# iBeacon.net
KiCad netlist of a schematic drawn in EAGLE
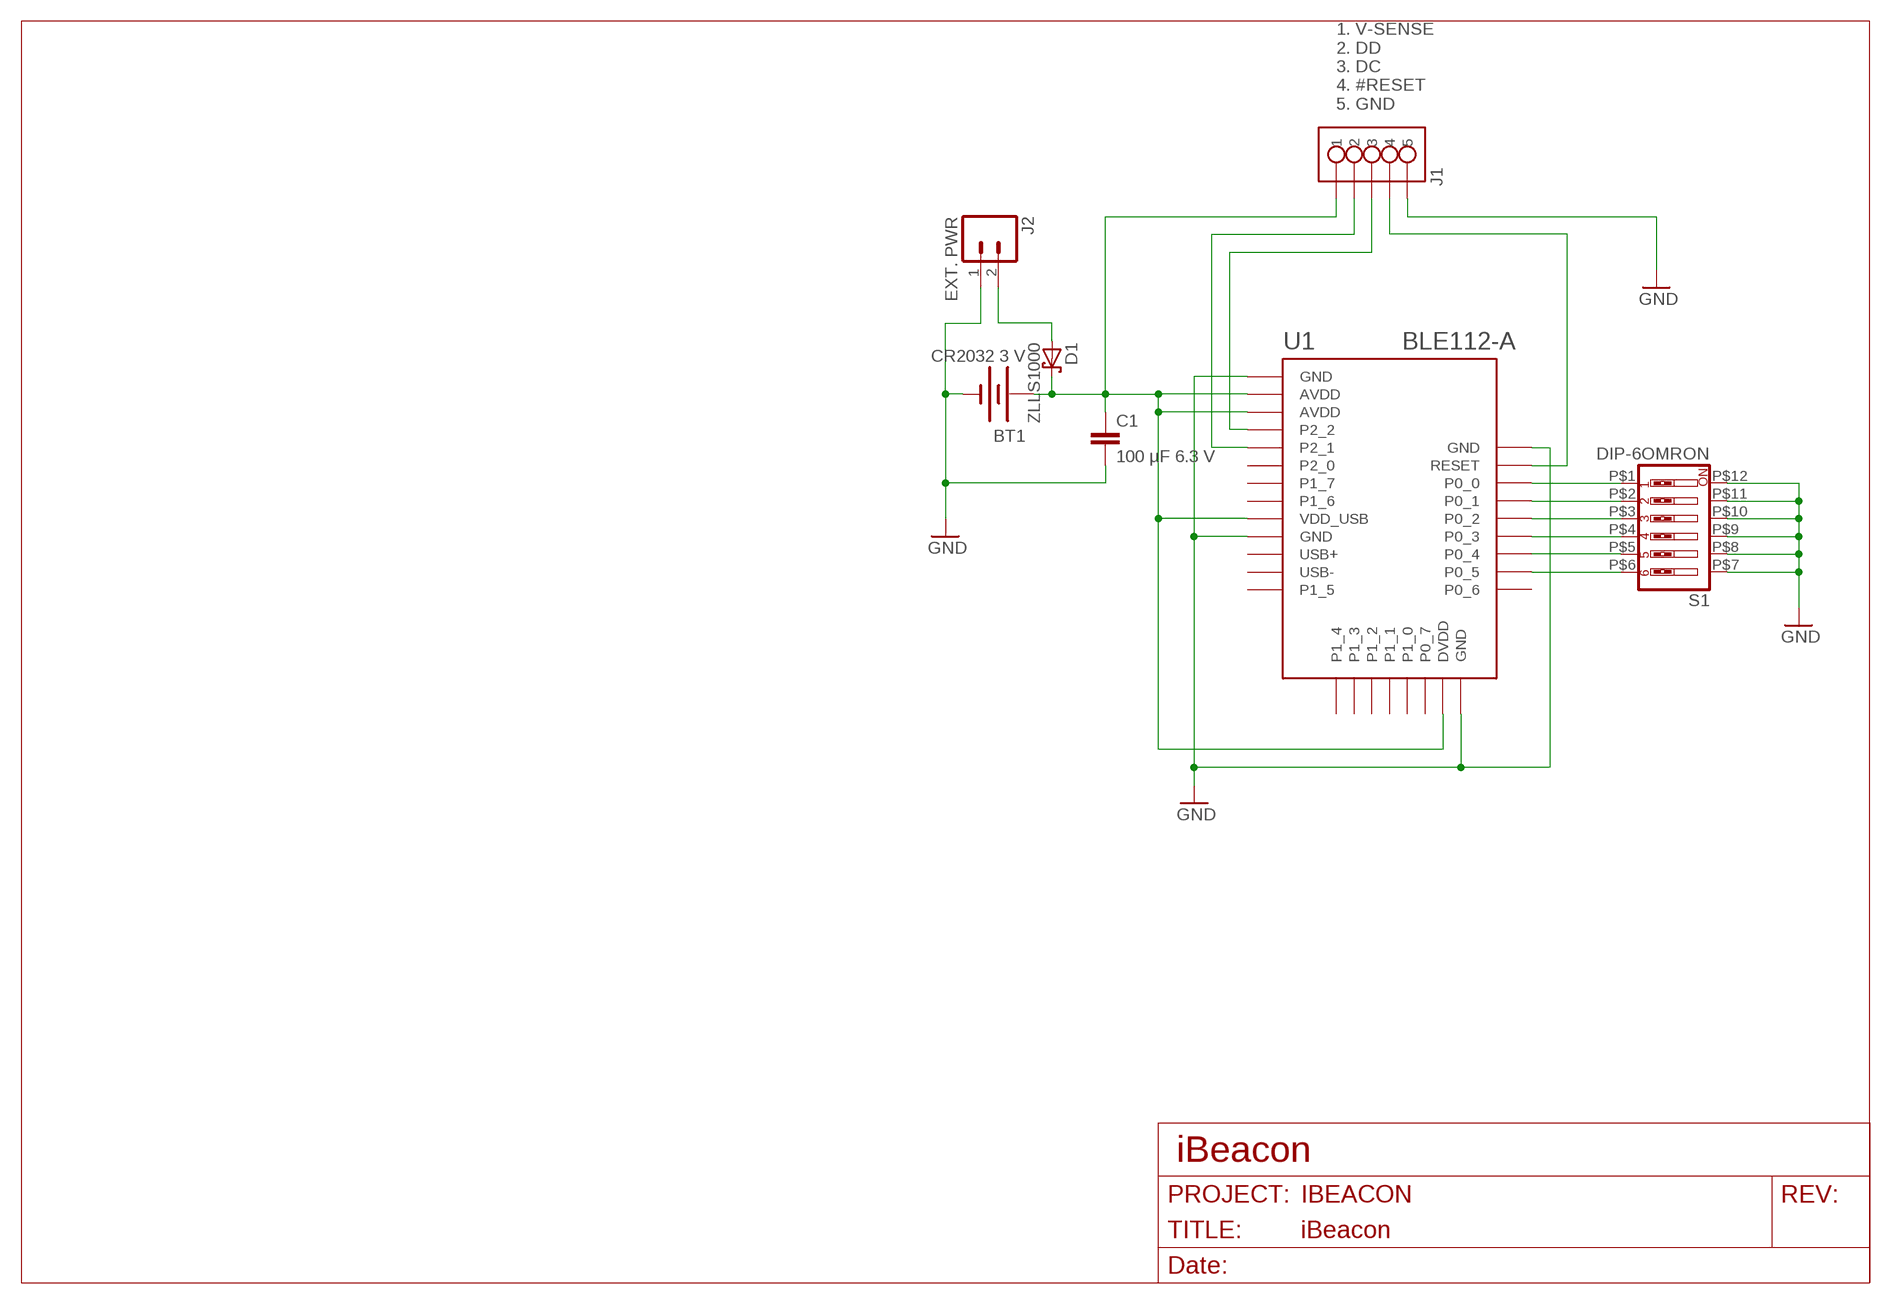
[diagram p0: schematic, sheet 1]

(export (version "E")
  (design (tool "Eeschema 10.0.6"))
  (components
    (comp (ref "BT1")
      (value "CR2032 3 V")
      (footprint "eagle-import:BATTCON_20MM")
      (libsource (lib "eagle-import") (part "BATTERY20SMD"))
    )
    (comp (ref "C1")
      (value "100 µF 6.3 V")
      (footprint "eagle-import:C1210K")
      (libsource (lib "eagle-import") (part "C-EUC1210K"))
    )
    (comp (ref "D1")
      (value "ZLLS1000")
      (footprint "eagle-import:SOT23")
      (libsource (lib "eagle-import") (part "BAS40"))
    )
    (comp (ref "IBEACON")
      (value "iBeacon")
      (footprint "eagle-import:DOCFIELD")
      (libsource (lib "eagle-import") (part "DOCFIELD_JWJ"))
    )
    (comp (ref "J1")
      (value "JST_SH_5")
      (footprint "eagle-import:JST_SH_5")
      (libsource (lib "eagle-import") (part "JST_SH_5"))
    )
    (comp (ref "J2")
      (value "EXT. PWR")
      (footprint "eagle-import:1X02")
      (libsource (lib "eagle-import") (part "M02PTH"))
    )
    (comp (ref "S1")
      (value "DIP-6OMRON")
      (footprint "eagle-import:OMRON_HALFPITCH_DIP_6")
      (libsource (lib "eagle-import") (part "DIP-6OMRON"))
    )
    (comp (ref "U1")
      (value "BLE112-A")
      (footprint "eagle-import:SF-BLUEGIGA_BLE112-A")
      (libsource (lib "eagle-import") (part "SF-BLUEGIGA_BLE112-A-VISUAL"))
    )
  )
  (nets
    (net (code "1") (name "GND") (class "Default")
      (node (ref "BT1") (pin "2") (pinfunction "-_2") (pintype "power_in"))
      (node (ref "C1") (pin "2") (pinfunction "2_2") (pintype "passive"))
      (node (ref "J1") (pin "P$5") (pinfunction "5_P$5") (pintype "bidirectional"))
      (node (ref "J2") (pin "1") (pinfunction "1_1") (pintype "passive"))
      (node (ref "S1") (pin "P$10") (pinfunction "10_P$10") (pintype "passive"))
      (node (ref "S1") (pin "P$11") (pinfunction "11_P$11") (pintype "passive"))
      (node (ref "S1") (pin "P$12") (pinfunction "12_P$12") (pintype "passive"))
      (node (ref "S1") (pin "P$7") (pinfunction "7_P$7") (pintype "passive"))
      (node (ref "S1") (pin "P$8") (pinfunction "8_P$8") (pintype "passive"))
      (node (ref "S1") (pin "P$9") (pinfunction "9_P$9") (pintype "passive"))
      (node (ref "U1") (pin "GND1") (pinfunction "GND_GND1") (pintype "power_in"))
      (node (ref "U1") (pin "GND2") (pinfunction "GND_GND2") (pintype "power_in"))
      (node (ref "U1") (pin "GND3") (pinfunction "GND_GND3") (pintype "power_in"))
      (node (ref "U1") (pin "GND4") (pinfunction "GND_GND4") (pintype "power_in"))
    )
    (net (code "2") (name "Net-(D1-A)") (class "Default")
      (node (ref "D1") (pin "1") (pinfunction "A_1") (pintype "passive"))
      (node (ref "J2") (pin "2") (pinfunction "2_2") (pintype "passive"))
    )
    (net (code "3") (name "Net-(D1-C)") (class "Default")
      (node (ref "BT1") (pin "1") (pinfunction "+_1") (pintype "power_in"))
      (node (ref "BT1") (pin "3") (pinfunction "+_3") (pintype "power_in"))
      (node (ref "C1") (pin "1") (pinfunction "1_1") (pintype "passive"))
      (node (ref "D1") (pin "3") (pinfunction "C_3") (pintype "passive"))
      (node (ref "J1") (pin "P$1") (pinfunction "1_P$1") (pintype "bidirectional"))
      (node (ref "U1") (pin "AVDD1") (pinfunction "AVDD_AVDD1") (pintype "power_in"))
      (node (ref "U1") (pin "AVDD2") (pinfunction "AVDD_AVDD2") (pintype "power_in"))
      (node (ref "U1") (pin "DVDD") (pinfunction "DVDD_DVDD") (pintype "power_in"))
      (node (ref "U1") (pin "VDD_USB") (pinfunction "VDD_USB_VDD_USB") (pintype "power_in"))
    )
    (net (code "4") (name "Net-(J1-2)") (class "Default")
      (node (ref "J1") (pin "P$2") (pinfunction "2_P$2") (pintype "bidirectional"))
      (node (ref "U1") (pin "P2_1") (pinfunction "P2_1_P2_1") (pintype "bidirectional"))
    )
    (net (code "5") (name "Net-(J1-3)") (class "Default")
      (node (ref "J1") (pin "P$3") (pinfunction "3_P$3") (pintype "bidirectional"))
      (node (ref "U1") (pin "P2_2") (pinfunction "P2_2_P2_2") (pintype "bidirectional"))
    )
    (net (code "6") (name "Net-(J1-4)") (class "Default")
      (node (ref "J1") (pin "P$4") (pinfunction "4_P$4") (pintype "bidirectional"))
      (node (ref "U1") (pin "RESET") (pinfunction "RESET_RESET") (pintype "input"))
    )
    (net (code "7") (name "Net-(S1-1)") (class "Default")
      (node (ref "S1") (pin "P$1") (pinfunction "1_P$1") (pintype "passive"))
      (node (ref "U1") (pin "P0_0") (pinfunction "P0_0_P0_0") (pintype "bidirectional"))
    )
    (net (code "8") (name "Net-(S1-2)") (class "Default")
      (node (ref "S1") (pin "P$2") (pinfunction "2_P$2") (pintype "passive"))
      (node (ref "U1") (pin "P0_1") (pinfunction "P0_1_P0_1") (pintype "bidirectional"))
    )
    (net (code "9") (name "Net-(S1-3)") (class "Default")
      (node (ref "S1") (pin "P$3") (pinfunction "3_P$3") (pintype "passive"))
      (node (ref "U1") (pin "P0_2") (pinfunction "P0_2_P0_2") (pintype "bidirectional"))
    )
    (net (code "10") (name "Net-(S1-4)") (class "Default")
      (node (ref "S1") (pin "P$4") (pinfunction "4_P$4") (pintype "passive"))
      (node (ref "U1") (pin "P0_3") (pinfunction "P0_3_P0_3") (pintype "bidirectional"))
    )
    (net (code "11") (name "Net-(S1-5)") (class "Default")
      (node (ref "S1") (pin "P$5") (pinfunction "5_P$5") (pintype "passive"))
      (node (ref "U1") (pin "P0_4") (pinfunction "P0_4_P0_4") (pintype "bidirectional"))
    )
    (net (code "12") (name "Net-(S1-6)") (class "Default")
      (node (ref "S1") (pin "P$6") (pinfunction "6_P$6") (pintype "passive"))
      (node (ref "U1") (pin "P0_5") (pinfunction "P0_5_P0_5") (pintype "bidirectional"))
    )
    (net (code "13") (name "unconnected-(U1-PadP0_6)") (class "Default")
      (node (ref "U1") (pin "P0_6") (pinfunction "P0_6_P0_6") (pintype "bidirectional"))
    )
    (net (code "14") (name "unconnected-(U1-PadP0_7)") (class "Default")
      (node (ref "U1") (pin "P0_7") (pinfunction "P0_7_P0_7") (pintype "bidirectional"))
    )
    (net (code "15") (name "unconnected-(U1-PadP1_0)") (class "Default")
      (node (ref "U1") (pin "P1_0") (pinfunction "P1_0_P1_0") (pintype "bidirectional"))
    )
    (net (code "16") (name "unconnected-(U1-PadP1_1)") (class "Default")
      (node (ref "U1") (pin "P1_1") (pinfunction "P1_1_P1_1") (pintype "bidirectional"))
    )
    (net (code "17") (name "unconnected-(U1-PadP1_2)") (class "Default")
      (node (ref "U1") (pin "P1_2") (pinfunction "P1_2_P1_2") (pintype "bidirectional"))
    )
    (net (code "18") (name "unconnected-(U1-PadP1_3)") (class "Default")
      (node (ref "U1") (pin "P1_3") (pinfunction "P1_3_P1_3") (pintype "bidirectional"))
    )
    (net (code "19") (name "unconnected-(U1-PadP1_4)") (class "Default")
      (node (ref "U1") (pin "P1_4") (pinfunction "P1_4_P1_4") (pintype "bidirectional"))
    )
    (net (code "20") (name "unconnected-(U1-PadP1_5)") (class "Default")
      (node (ref "U1") (pin "P1_5") (pinfunction "P1_5_P1_5") (pintype "bidirectional"))
    )
    (net (code "21") (name "unconnected-(U1-PadP1_6)") (class "Default")
      (node (ref "U1") (pin "P1_6") (pinfunction "P1_6_P1_6") (pintype "bidirectional"))
    )
    (net (code "22") (name "unconnected-(U1-PadP1_7)") (class "Default")
      (node (ref "U1") (pin "P1_7") (pinfunction "P1_7_P1_7") (pintype "bidirectional"))
    )
    (net (code "23") (name "unconnected-(U1-PadP2_0)") (class "Default")
      (node (ref "U1") (pin "P2_0") (pinfunction "P2_0_P2_0") (pintype "bidirectional"))
    )
    (net (code "24") (name "unconnected-(U1-PadUSB+)") (class "Default")
      (node (ref "U1") (pin "USB+") (pinfunction "USB+_USB+") (pintype "bidirectional"))
    )
    (net (code "25") (name "unconnected-(U1-PadUSB-)") (class "Default")
      (node (ref "U1") (pin "USB-") (pinfunction "USB-_USB-") (pintype "bidirectional"))
    )
  )
)
